# bidirectional_audio_v4_0_AFE.net
KiCad netlist of a schematic drawn in Altium Designer
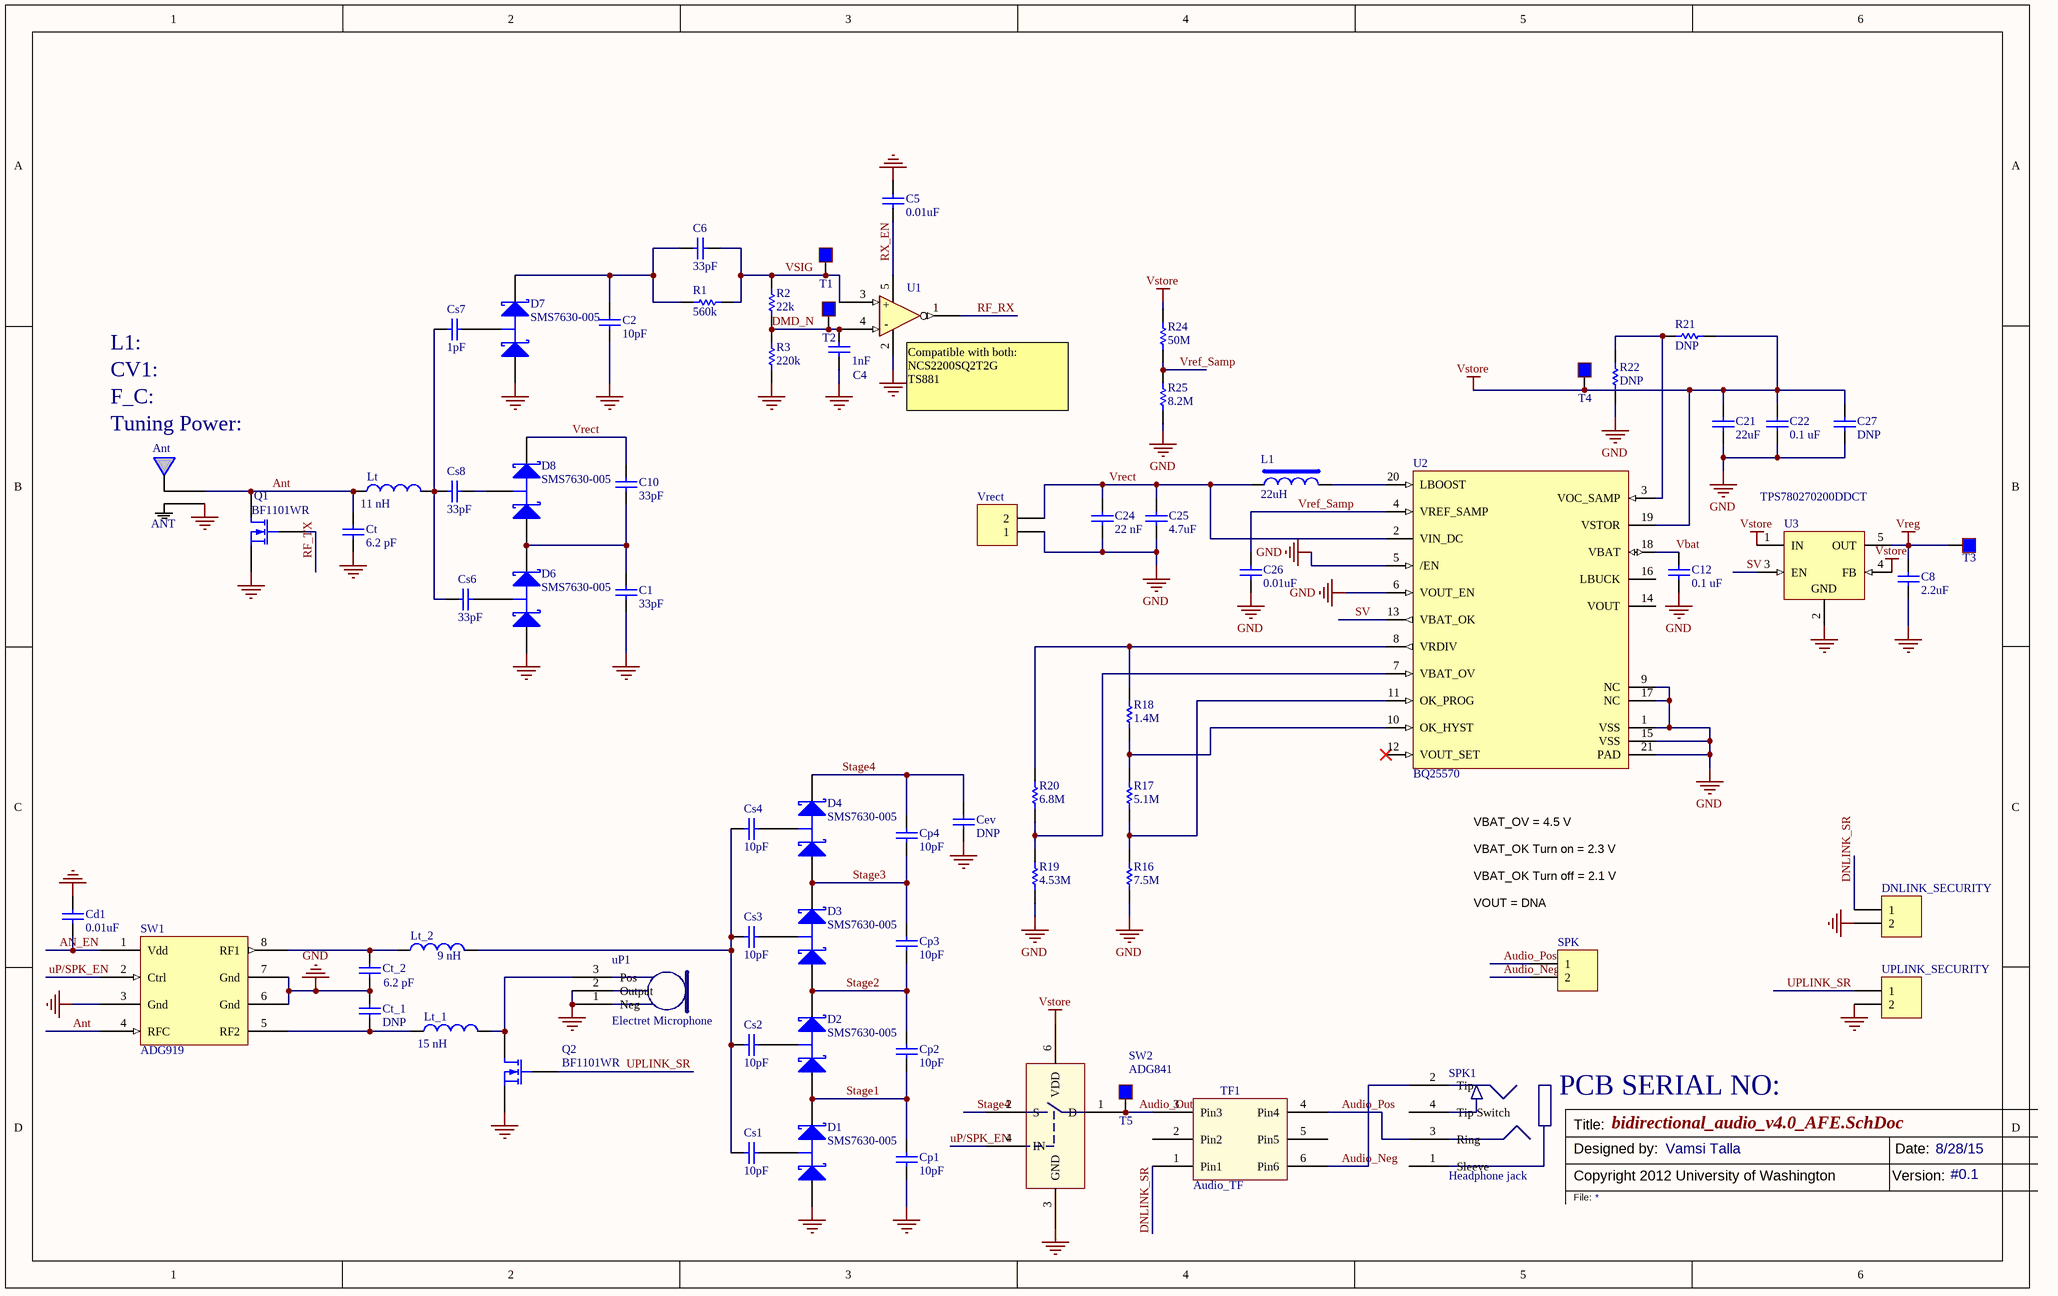
[diagram p0: bidirectional_audio_v4.0_AFE.SchDoc]

(export (version "E")
  (design (tool "Eeschema 10.0.6"))
  (components
    (comp (ref "Ant")
      (value "ANT")
      (footprint "PIFA_915MHz")
      (libsource (lib "bidirectional_audio") (part "ANT"))
    )
    (comp (ref "C1")
      (value "33pF")
      (footprint "0402")
      (description "Ceramic Capacitor (Surface Mount)")
      (fields
        (field (name "DIGI-KEY PART NUMBER") "712-1297-1-ND")
        (field (name "MANUFACTURER") "Johanson Technology Inc.")
      )
      (libsource (lib "WISP_AD10") (part "Cap"))
    )
    (comp (ref "C2")
      (value "10pF")
      (footprint "0402")
      (description "Ceramic Capacitor (Surface Mount)")
      (fields
        (field (name "DIGI-KEY PART NUMBER") "712-1252-1-ND")
        (field (name "MANUFACTURER") "Johanson Technology Inc.")
      )
      (libsource (lib "WISP_AD10") (part "Cap"))
    )
    (comp (ref "C4")
      (value "1nF")
      (footprint "0402")
      (description "Ceramic Capacitor (Surface Mount)")
      (fields
        (field (name "DIGI-KEY PART NUMBER") "490-6189-1-ND")
        (field (name "MANUFACTURER") "Murata Electronics North America")
      )
      (libsource (lib "WISP_AD10") (part "Cap"))
    )
    (comp (ref "C5")
      (value "0.01uF")
      (footprint "0402")
      (description "Ceramic Capacitor (Surface Mount)")
      (fields
        (field (name "DIGI-KEY PART NUMBER") "1276-1495-1-ND")
        (field (name "MANUFACTURER") "Samsung Electro-Mechanics America, Inc.")
      )
      (libsource (lib "WISP_AD10") (part "Cap"))
    )
    (comp (ref "C6")
      (value "33pF")
      (footprint "0402")
      (description "Ceramic Capacitor (Surface Mount)")
      (fields
        (field (name "DIGI-KEY PART NUMBER") "712-1297-1-ND")
        (field (name "MANUFACTURER") "Johanson Technology Inc.")
      )
      (libsource (lib "WISP_AD10") (part "Cap"))
    )
    (comp (ref "C8")
      (value "2.2uF")
      (footprint "0402")
      (description "Ceramic Capacitor (Surface Mount)")
      (fields
        (field (name "DIGI-KEY PART NUMBER") "478-7885-1-ND")
        (field (name "MANUFACTURER") "AVX Corporation")
      )
      (libsource (lib "WISP_AD10") (part "Cap"))
    )
    (comp (ref "C10")
      (value "33pF")
      (footprint "0402")
      (description "Ceramic Capacitor (Surface Mount)")
      (fields
        (field (name "DIGI-KEY PART NUMBER") "712-1297-1-ND")
        (field (name "MANUFACTURER") "Johanson Technology Inc.")
      )
      (libsource (lib "WISP_AD10") (part "Cap"))
    )
    (comp (ref "C12")
      (value "0.1 uF")
      (footprint "0402")
      (description "Ceramic Capacitor (Surface Mount)")
      (fields
        (field (name "DIGI-KEY PART NUMBER") "490-6327-1-ND")
        (field (name "MANUFACTURER") "Murata Electronics North America")
      )
      (libsource (lib "WISP_AD10") (part "Cap"))
    )
    (comp (ref "C21")
      (value "22uF")
      (footprint "0805-W")
      (description "Ceramic Capacitor (Surface Mount)")
      (fields
        (field (name "DIGI-KEY PART NUMBER") "1276-2867-1-ND")
        (field (name "MANUFACTURER") "Samsung Electro-Mechanics America, Inc.")
      )
      (libsource (lib "WISP_AD10") (part "Cap"))
    )
    (comp (ref "C22")
      (value "0.1 uF")
      (footprint "0402")
      (description "Ceramic Capacitor (Surface Mount)")
      (fields
        (field (name "DIGI-KEY PART NUMBER") "490-6327-1-ND")
        (field (name "MANUFACTURER") "Murata Electronics North America")
      )
      (libsource (lib "WISP_AD10") (part "Cap"))
    )
    (comp (ref "C24")
      (value "22 nF")
      (footprint "0402")
      (description "Ceramic Capacitor (Surface Mount)")
      (fields
        (field (name "DIGI-KEY PART NUMBER") "478-3666-1-ND")
        (field (name "MANUFACTURER") "AVX Corporation")
      )
      (libsource (lib "WISP_AD10") (part "Cap"))
    )
    (comp (ref "C25")
      (value "4.7uF")
      (footprint "0402")
      (description "Ceramic Capacitor (Surface Mount)")
      (fields
        (field (name "DIGI-KEY PART NUMBER") "445-5947-1-ND")
        (field (name "MANUFACTURER") "TDK Corporation")
      )
      (libsource (lib "WISP_AD10") (part "Cap"))
    )
    (comp (ref "C26")
      (value "0.01uF")
      (footprint "0402")
      (description "Ceramic Capacitor (Surface Mount)")
      (fields
        (field (name "DIGI-KEY PART NUMBER") "1276-1495-1-ND")
        (field (name "MANUFACTURER") "Samsung Electro-Mechanics America, Inc.")
      )
      (libsource (lib "WISP_AD10") (part "Cap"))
    )
    (comp (ref "C27")
      (value "DNP")
      (footprint "0805-W")
      (description "Ceramic Capacitor (Surface Mount)")
      (fields
        (field (name "MANUFACTURER") "Generic Ceramic Chip Cap (TBD)")
        (field (name "Comment") "Cstore2")
      )
      (libsource (lib "WISP_AD10") (part "Cap"))
    )
    (comp (ref "Cd1")
      (value "0.01uF")
      (footprint "0402")
      (description "Ceramic Capacitor (Surface Mount)")
      (fields
        (field (name "DIGI-KEY PART NUMBER") "1276-1495-1-ND")
        (field (name "MANUFACTURER") "Samsung Electro-Mechanics America, Inc.")
      )
      (libsource (lib "WISP_AD10") (part "Cap"))
    )
    (comp (ref "Cev")
      (value "DNP")
      (footprint "0402")
      (description "Ceramic Capacitor (Surface Mount)")
      (fields
        (field (name "MANUFACTURER") "Generic Ceramic Chip Cap (TBD)")
        (field (name "Comment") "Cout_env")
      )
      (libsource (lib "WISP_AD10") (part "Cap"))
    )
    (comp (ref "Cp1")
      (value "10pF")
      (footprint "0402")
      (description "Ceramic Capacitor (Surface Mount)")
      (fields
        (field (name "DIGI-KEY PART NUMBER") "712-1252-1-ND")
        (field (name "MANUFACTURER") "Johanson Technology Inc.")
      )
      (libsource (lib "WISP_AD10") (part "Cap"))
    )
    (comp (ref "Cp2")
      (value "10pF")
      (footprint "0402")
      (description "Ceramic Capacitor (Surface Mount)")
      (fields
        (field (name "DIGI-KEY PART NUMBER") "712-1252-1-ND")
        (field (name "MANUFACTURER") "Johanson Technology Inc.")
      )
      (libsource (lib "WISP_AD10") (part "Cap"))
    )
    (comp (ref "Cp3")
      (value "10pF")
      (footprint "0402")
      (description "Ceramic Capacitor (Surface Mount)")
      (fields
        (field (name "DIGI-KEY PART NUMBER") "712-1252-1-ND")
        (field (name "MANUFACTURER") "Johanson Technology Inc.")
      )
      (libsource (lib "WISP_AD10") (part "Cap"))
    )
    (comp (ref "Cp4")
      (value "10pF")
      (footprint "0402")
      (description "Ceramic Capacitor (Surface Mount)")
      (fields
        (field (name "DIGI-KEY PART NUMBER") "712-1252-1-ND")
        (field (name "MANUFACTURER") "Johanson Technology Inc.")
      )
      (libsource (lib "WISP_AD10") (part "Cap"))
    )
    (comp (ref "Cs1")
      (value "10pF")
      (footprint "0402")
      (description "Ceramic Capacitor (Surface Mount)")
      (fields
        (field (name "DIGI-KEY PART NUMBER") "712-1252-1-ND")
        (field (name "MANUFACTURER") "Johanson Technology Inc.")
      )
      (libsource (lib "WISP_AD10") (part "Cap"))
    )
    (comp (ref "Cs2")
      (value "10pF")
      (footprint "0402")
      (description "Ceramic Capacitor (Surface Mount)")
      (fields
        (field (name "DIGI-KEY PART NUMBER") "712-1252-1-ND")
        (field (name "MANUFACTURER") "Johanson Technology Inc.")
      )
      (libsource (lib "WISP_AD10") (part "Cap"))
    )
    (comp (ref "Cs3")
      (value "10pF")
      (footprint "0402")
      (description "Ceramic Capacitor (Surface Mount)")
      (fields
        (field (name "DIGI-KEY PART NUMBER") "712-1252-1-ND")
        (field (name "MANUFACTURER") "Johanson Technology Inc.")
      )
      (libsource (lib "WISP_AD10") (part "Cap"))
    )
    (comp (ref "Cs4")
      (value "10pF")
      (footprint "0402")
      (description "Ceramic Capacitor (Surface Mount)")
      (fields
        (field (name "DIGI-KEY PART NUMBER") "712-1252-1-ND")
        (field (name "MANUFACTURER") "Johanson Technology Inc.")
      )
      (libsource (lib "WISP_AD10") (part "Cap"))
    )
    (comp (ref "Cs6")
      (value "33pF")
      (footprint "0402")
      (description "Ceramic Capacitor (Surface Mount)")
      (fields
        (field (name "DIGI-KEY PART NUMBER") "712-1297-1-ND")
        (field (name "MANUFACTURER") "Johanson Technology Inc.")
      )
      (libsource (lib "WISP_AD10") (part "Cap"))
    )
    (comp (ref "Cs7")
      (value "1pF")
      (footprint "0402")
      (description "Ceramic Capacitor (Surface Mount)")
      (fields
        (field (name "DIGI-KEY PART NUMBER") "712-1266-1-ND")
        (field (name "MANUFACTURER") "Johanson Technology Inc.")
      )
      (libsource (lib "WISP_AD10") (part "Cap"))
    )
    (comp (ref "Cs8")
      (value "33pF")
      (footprint "0402")
      (description "Ceramic Capacitor (Surface Mount)")
      (fields
        (field (name "DIGI-KEY PART NUMBER") "712-1297-1-ND")
        (field (name "MANUFACTURER") "Johanson Technology Inc.")
      )
      (libsource (lib "WISP_AD10") (part "Cap"))
    )
    (comp (ref "Ct")
      (value "6.2 pF")
      (footprint "0402")
      (description "Ceramic Capacitor (Surface Mount)")
      (fields
        (field (name "DIGI-KEY PART NUMBER") "712-1290-1-ND")
        (field (name "MANUFACTURER") "Johanson Technology Inc.")
      )
      (libsource (lib "WISP_AD10") (part "Cap"))
    )
    (comp (ref "Ct_1")
      (value "DNP")
      (footprint "0402")
      (description "Ceramic Capacitor (Surface Mount)")
      (fields (field (name "MANUFACTURER") "Generic Ceramic Chip Cap (TBD)") (field (name "Comment") "Cap"))
      (libsource (lib "WISP_AD10") (part "Cap"))
    )
    (comp (ref "Ct_2")
      (value "6.2 pF")
      (footprint "0402")
      (description "Ceramic Capacitor (Surface Mount)")
      (fields
        (field (name "DIGI-KEY PART NUMBER") "712-1290-1-ND")
        (field (name "MANUFACTURER") "Johanson Technology Inc.")
      )
      (libsource (lib "WISP_AD10") (part "Cap"))
    )
    (comp (ref "D1")
      (value "SMS7630-005")
      (footprint "SOT23 - N")
      (description "Agilent Schottky Diode, Two in Series, Small Package SOT-323")
      (fields
        (field (name "DIGI-KEY PART NUMBER") "863-1699-1-ND")
        (field (name "MANUFACTURER") "Skyworks Solutions Inc.")
      )
      (libsource (lib "WISP_AD10") (part "SMS7630-005"))
    )
    (comp (ref "D2")
      (value "SMS7630-005")
      (footprint "SOT23 - N")
      (description "Agilent Schottky Diode, Two in Series, Small Package SOT-323")
      (fields
        (field (name "DIGI-KEY PART NUMBER") "863-1699-1-ND")
        (field (name "MANUFACTURER") "Skyworks Solutions Inc.")
      )
      (libsource (lib "WISP_AD10") (part "SMS7630-005"))
    )
    (comp (ref "D3")
      (value "SMS7630-005")
      (footprint "SOT23 - N")
      (description "Agilent Schottky Diode, Two in Series, Small Package SOT-323")
      (fields
        (field (name "DIGI-KEY PART NUMBER") "863-1699-1-ND")
        (field (name "MANUFACTURER") "Skyworks Solutions Inc.")
      )
      (libsource (lib "WISP_AD10") (part "SMS7630-005"))
    )
    (comp (ref "D4")
      (value "SMS7630-005")
      (footprint "SOT23 - N")
      (description "Agilent Schottky Diode, Two in Series, Small Package SOT-323")
      (fields
        (field (name "DIGI-KEY PART NUMBER") "863-1699-1-ND")
        (field (name "MANUFACTURER") "Skyworks Solutions Inc.")
      )
      (libsource (lib "WISP_AD10") (part "SMS7630-005"))
    )
    (comp (ref "D6")
      (value "SMS7630-005")
      (footprint "SOT23 - N")
      (description "Agilent Schottky Diode, Two in Series, Small Package SOT-323")
      (fields
        (field (name "DIGI-KEY PART NUMBER") "863-1699-1-ND")
        (field (name "MANUFACTURER") "Skyworks Solutions Inc.")
      )
      (libsource (lib "WISP_AD10") (part "SMS7630-005"))
    )
    (comp (ref "D7")
      (value "SMS7630-005")
      (footprint "SOT23 - N")
      (description "Agilent Schottky Diode, Two in Series, Small Package SOT-323")
      (fields
        (field (name "DIGI-KEY PART NUMBER") "863-1699-1-ND")
        (field (name "MANUFACTURER") "Skyworks Solutions Inc.")
      )
      (libsource (lib "WISP_AD10") (part "SMS7630-005"))
    )
    (comp (ref "D8")
      (value "SMS7630-005")
      (footprint "SOT23 - N")
      (description "Agilent Schottky Diode, Two in Series, Small Package SOT-323")
      (fields
        (field (name "DIGI-KEY PART NUMBER") "863-1699-1-ND")
        (field (name "MANUFACTURER") "Skyworks Solutions Inc.")
      )
      (libsource (lib "WISP_AD10") (part "SMS7630-005"))
    )
    (comp (ref "DNLINK_SECURITY")
      (value "MHDR1X2")
      (footprint "MHDR1X2")
      (description "Header, 2-Pin")
      (fields
        (field (name "DIGI-KEY PART NUMBER") "609-4434-ND")
        (field (name "MANUFACTURER") "FCI")
        (field (name "PUBLISHER") "Altium Limited")
      )
      (libsource (lib "Miscellaneous Connectors") (part "MHDR1X2"))
    )
    (comp (ref "L1")
      (value "22uH")
      (footprint "LPS4018")
      (description "Inductor (Surface Mount)")
      (fields (field (name "DIGI-KEY PART NUMBER") "NA") (field (name "MANUFACTURER") "Coil Craft"))
      (libsource (lib "WISP_AD10") (part "Ind_LPS4018"))
    )
    (comp (ref "Lt")
      (value "11 nH")
      (footprint "0402")
      (description "Inductor (Surface Mount)")
      (fields (field (name "MANUFACTURER PART NUMBER") "0402HP-11NXGE") (field (name "Comment") "L_Ant_tune"))
      (libsource (lib "WISP_AD10") (part "Ind"))
    )
    (comp (ref "Lt_1")
      (value "15 nH")
      (footprint "0402")
      (description "Inductor (Surface Mount)")
      (fields (field (name "MANUFACTURER PART NUMBER") "0402HP-15NXGE") (field (name "Comment") "Ind"))
      (libsource (lib "WISP_AD10") (part "Ind"))
    )
    (comp (ref "Lt_2")
      (value "9 nH")
      (footprint "0402")
      (description "Inductor (Surface Mount)")
      (fields (field (name "MANUFACTURER PART NUMBER") "0402HP-9N0XGE") (field (name "Comment") "Ind"))
      (libsource (lib "WISP_AD10") (part "Ind"))
    )
    (comp (ref "Q1")
      (value "BF1101WR")
      (footprint "SOT343R")
      (description "N-Channel Dual-Gate Mos-Fets MOSFET, SOT343R")
      (fields
        (field (name "DIGI-KEY PART NUMBER") "568-6140-1-ND")
        (field (name "MANUFACTURER PART NUMBER") "BF1101WR,115")
      )
      (libsource (lib "WISP_AD10") (part "BF1101WR"))
    )
    (comp (ref "Q2")
      (value "BF1101WR")
      (footprint "SOT343R")
      (description "N-Channel Dual-Gate Mos-Fets MOSFET, SOT343R")
      (fields
        (field (name "DIGI-KEY PART NUMBER") "568-6140-1-ND")
        (field (name "MANUFACTURER PART NUMBER") "BF1101WR,115")
      )
      (libsource (lib "WISP_AD10") (part "BF1101WR"))
    )
    (comp (ref "R1")
      (value "560k")
      (footprint "0402")
      (description "Chip Resistor (Surface Mount)")
      (fields
        (field (name "MANUFACTURER") "Yageo")
        (field (name "MANUFACTURER PART NUMBER") "RC0402FR-07560KL")
      )
      (libsource (lib "WISP_AD10") (part "Res"))
    )
    (comp (ref "R2")
      (value "22k")
      (footprint "0402")
      (description "Chip Resistor (Surface Mount)")
      (fields
        (field (name "MANUFACTURER") "Yageo")
        (field (name "MANUFACTURER PART NUMBER") "RC0402FR-0722KL")
      )
      (libsource (lib "WISP_AD10") (part "Res"))
    )
    (comp (ref "R3")
      (value "220k")
      (footprint "0402")
      (description "Chip Resistor (Surface Mount)")
      (fields
        (field (name "MANUFACTURER") "Yageo")
        (field (name "MANUFACTURER PART NUMBER") "RC0402FR-07220KL")
      )
      (libsource (lib "WISP_AD10") (part "Res"))
    )
    (comp (ref "R16")
      (value "7.5M")
      (footprint "0402")
      (description "Chip Resistor (Surface Mount)")
      (fields
        (field (name "MANUFACTURER") "Vishay Dale")
        (field (name "MANUFACTURER PART NUMBER") "CRCW04027M50JNED")
      )
      (libsource (lib "WISP_AD10") (part "Res"))
    )
    (comp (ref "R17")
      (value "5.1M")
      (footprint "0402")
      (description "Chip Resistor (Surface Mount)")
      (fields
        (field (name "MANUFACTURER") "Vishay Dale")
        (field (name "MANUFACTURER PART NUMBER") "CRCW04025M10JNED")
      )
      (libsource (lib "WISP_AD10") (part "Res"))
    )
    (comp (ref "R18")
      (value "1.4M")
      (footprint "0402")
      (description "Chip Resistor (Surface Mount)")
      (fields
        (field (name "MANUFACTURER") "Vishay Dale")
        (field (name "MANUFACTURER PART NUMBER") "CRCW04021M40FKED")
      )
      (libsource (lib "WISP_AD10") (part "Res"))
    )
    (comp (ref "R19")
      (value "4.53M")
      (footprint "0402")
      (description "Chip Resistor (Surface Mount)")
      (fields
        (field (name "MANUFACTURER") "Vishay Dale")
        (field (name "MANUFACTURER PART NUMBER") "CRCW04024M53FKED")
      )
      (libsource (lib "WISP_AD10") (part "Res"))
    )
    (comp (ref "R20")
      (value "6.8M")
      (footprint "0402")
      (description "Chip Resistor (Surface Mount)")
      (fields
        (field (name "MANUFACTURER") "Samsung Electro-Mechanics America, Inc.")
        (field (name "MANUFACTURER PART NUMBER") "RC1005J685CS")
      )
      (libsource (lib "WISP_AD10") (part "Res"))
    )
    (comp (ref "R21")
      (value "DNP")
      (footprint "0402")
      (description "Chip Resistor (Surface Mount)")
      (fields (field (name "MANUFACTURER") "Generic Chip Res (TBD)") (field (name "Comment") "R_80%"))
      (libsource (lib "WISP_AD10") (part "Res"))
    )
    (comp (ref "R22")
      (value "DNP")
      (footprint "0402")
      (description "Chip Resistor (Surface Mount)")
      (fields (field (name "MANUFACTURER") "Generic Chip Res (TBD)") (field (name "Comment") "R_50%"))
      (libsource (lib "WISP_AD10") (part "Res"))
    )
    (comp (ref "R24")
      (value "50M")
      (footprint "0402")
      (description "Chip Resistor (Surface Mount)")
      (fields
        (field (name "MANUFACTURER") "Stackpole Electronics Inc.")
        (field (name "MANUFACTURER PART NUMBER") "HMC0402JT50M0")
      )
      (libsource (lib "WISP_AD10") (part "Res"))
    )
    (comp (ref "R25")
      (value "8.2M")
      (footprint "0402")
      (description "Chip Resistor (Surface Mount)")
      (fields
        (field (name "MANUFACTURER") "Vishay Dale")
        (field (name "MANUFACTURER PART NUMBER") "CRCW04028M20JNED")
      )
      (libsource (lib "WISP_AD10") (part "Res"))
    )
    (comp (ref "SPK")
      (value "MHDR1X2")
      (footprint "MHDR1X2")
      (description "Header, 2-Pin")
      (fields
        (field (name "DIGI-KEY PART NUMBER") "609-4434-ND")
        (field (name "MANUFACTURER") "FCI")
        (field (name "PUBLISHER") "Altium Limited")
      )
      (libsource (lib "Miscellaneous Connectors") (part "MHDR1X2"))
    )
    (comp (ref "SPK1")
      (value "Headphone jack")
      (footprint "CONN_JACK")
      (fields
        (field (name "DIGI-KEY PART NUMBER") "CP-3524SJGRCT-ND")
        (field (name "MANUFACTURER") "CUI Inc.")
        (field (name "MANUFACTURER PART NUMBER") "SJ-3524-SMT-TR-GR")
      )
      (libsource (lib "bidirectional_audio") (part "CONN_JACK"))
    )
    (comp (ref "SW1")
      (value "ADG919")
      (footprint "MSOP_8pin")
      (description "RF 2:1 MUX/SPDT Reflective")
      (fields
        (field (name "DIGI-KEY PART NUMBER") "ADG919BRMZ-ND")
        (field (name "MANUFACTURER PART NUMBER") "ADG919BRMZ")
      )
      (libsource (lib "WispLib") (part "ADG919"))
    )
    (comp (ref "SW2")
      (value "ADG841")
      (footprint "SC70-6")
      (description "Audio Switch")
      (fields
        (field (name "MANUFACTURER PART NUMBER") "ADG841YKSZ-500RL7")
        (field (name "MANUFACTURER") "Analog Devices Inc.")
      )
      (libsource (lib "bidirectional_audio") (part "ADG841"))
    )
    (comp (ref "T1")
      (value "Test Point SMT")
      (footprint "SMT_TESTPOINT_2MM")
      (description "Test Point, Flat Pad")
      (fields
        (field (name "DIGI-KEY PART NUMBER") "A106145CT-ND")
        (field (name "MANUFACTURER PART NUMBER") "1625854-3")
      )
      (libsource (lib "WISP_AD10") (part "Test Point SMT"))
    )
    (comp (ref "T2")
      (value "Test Point SMT")
      (footprint "SMT_TESTPOINT_2MM")
      (description "Test Point, Flat Pad")
      (fields
        (field (name "DIGI-KEY PART NUMBER") "A106145CT-ND")
        (field (name "MANUFACTURER PART NUMBER") "1625854-3")
      )
      (libsource (lib "WISP_AD10") (part "Test Point SMT"))
    )
    (comp (ref "T3")
      (value "Test Point SMT")
      (footprint "SMT_TESTPOINT_2MM")
      (description "Test Point, Flat Pad")
      (fields
        (field (name "DIGI-KEY PART NUMBER") "A106145CT-ND")
        (field (name "MANUFACTURER PART NUMBER") "1625854-3")
      )
      (libsource (lib "") (part "Test Point SMT_1"))
    )
    (comp (ref "T4")
      (value "Test Point SMT")
      (footprint "SMT_TESTPOINT_2MM")
      (description "Test Point, Flat Pad")
      (fields
        (field (name "DIGI-KEY PART NUMBER") "A106145CT-ND")
        (field (name "MANUFACTURER PART NUMBER") "1625854-3")
      )
      (libsource (lib "WISP_AD10") (part "Test Point SMT"))
    )
    (comp (ref "T5")
      (value "Test Point SMT")
      (footprint "SMT_TESTPOINT_2MM")
      (description "Test Point, Flat Pad")
      (fields
        (field (name "DIGI-KEY PART NUMBER") "A106145CT-ND")
        (field (name "MANUFACTURER PART NUMBER") "1625854-3")
      )
      (libsource (lib "WISP_AD10") (part "Test Point SMT"))
    )
    (comp (ref "TF1")
      (value "Audio_TF")
      (footprint "Audio_TF")
      (description "Audio Transformer by Triad")
      (fields
        (field (name "DIGI-KEY PART NUMBER") "237-1146-ND")
        (field (name "MANUFACTURER") "Triad Magnetics")
      )
      (libsource (lib "bidirectional_audio") (part "Audio_TF"))
    )
    (comp (ref "U1")
      (value "Comparator")
      (footprint "SC70-5")
      (description "6uA Comparator")
      (fields
        (field (name "DIGI-KEY PART NUMBER") "568-7526-1-ND")
        (field (name "MANUFACTURER") "NXP Semiconductors")
      )
      (libsource (lib "WISP_AD10") (part "NCS2200"))
    )
    (comp (ref "U2")
      (value "BQ25570")
      (footprint "BQ25570")
      (description "Boost Charger")
      (fields
        (field (name "DIGI-KEY PART NUMBER") "296-37014-1-ND")
        (field (name "MANUFACTURER") "Texas Instruments")
      )
      (libsource (lib "WISP_AD10") (part "BQ25570"))
    )
    (comp (ref "U3")
      (value "TPS780270200DDCT")
      (footprint "TI-DDC5_L")
      (fields
        (field (name "MANUFACTURER") "Texas Instruments")
        (field (name "DIGI-KEY PART NUMBER") "296-32564-1-ND")
      )
      (libsource (lib "Altium Content Vault") (part "CMP-0394-01119-1"))
    )
    (comp (ref "uP1")
      (value "Electret Microphone")
      (footprint "uP_23024")
      (fields
        (field (name "DIGI-KEY PART NUMBER") "423-1160-ND")
        (field (name "MANUFACTURER") "Knowles")
        (field (name "MANUFACTURER PART NUMBER") "EK-23024-000")
      )
      (libsource (lib "bidirectional_audio") (part "UP_Knowles_23024"))
    )
    (comp (ref "UPLINK_SECURITY")
      (value "MHDR1X2")
      (footprint "MHDR1X2")
      (description "Header, 2-Pin")
      (fields
        (field (name "DIGI-KEY PART NUMBER") "609-4434-ND")
        (field (name "MANUFACTURER") "FCI")
        (field (name "PUBLISHER") "Altium Limited")
      )
      (libsource (lib "Miscellaneous Connectors") (part "MHDR1X2"))
    )
    (comp (ref "Vrect")
      (value "MHDR1X2")
      (footprint "MHDR1X2")
      (description "Header, 2-Pin")
      (fields
        (field (name "DIGI-KEY PART NUMBER") "609-4434-ND")
        (field (name "MANUFACTURER") "FCI")
        (field (name "PUBLISHER") "Altium Limited")
      )
      (libsource (lib "") (part "MHDR1X2_1"))
    )
  )
  (nets
    (net (code "1") (name "/AN_EN") (class "Default")
      (node (ref "Cd1") (pin "1") (pinfunction "1_1") (pintype "passive"))
      (node (ref "SW1") (pin "1") (pinfunction "Vdd_1") (pintype "power_in"))
    )
    (net (code "2") (name "/Ant") (class "Default")
      (node (ref "Ant") (pin "1") (pinfunction "Feed_1") (pintype "passive"))
      (node (ref "Ct") (pin "1") (pinfunction "1_1") (pintype "passive"))
      (node (ref "Lt") (pin "1") (pinfunction "1_1") (pintype "passive"))
      (node (ref "Q1") (pin "2") (pinfunction "D_2") (pintype "passive"))
      (node (ref "SW1") (pin "4") (pinfunction "RFC_4") (pintype "input"))
    )
    (net (code "3") (name "/Audio_Neg") (class "Default")
      (node (ref "SPK") (pin "2") (pinfunction "2_2") (pintype "passive"))
      (node (ref "SPK1") (pin "2") (pinfunction "Tip_2") (pintype "passive"))
      (node (ref "TF1") (pin "6") (pinfunction "Pin6_6") (pintype "passive"))
    )
    (net (code "4") (name "/Audio_Out") (class "Default")
      (node (ref "SW2") (pin "1") (pinfunction "D_1") (pintype "passive"))
      (node (ref "T5") (pin "1") (pintype "passive"))
      (node (ref "TF1") (pin "3") (pinfunction "Pin3_3") (pintype "passive"))
    )
    (net (code "5") (name "/Audio_Pos") (class "Default")
      (node (ref "SPK") (pin "1") (pinfunction "1_1") (pintype "passive"))
      (node (ref "SPK1") (pin "3") (pinfunction "Ring_3") (pintype "passive"))
      (node (ref "TF1") (pin "4") (pinfunction "Pin4_4") (pintype "passive"))
    )
    (net (code "6") (name "/DMD_N") (class "Default")
      (node (ref "C4") (pin "1") (pinfunction "1_1") (pintype "passive"))
      (node (ref "R2") (pin "1") (pinfunction "1_1") (pintype "passive"))
      (node (ref "R3") (pin "2") (pinfunction "2_2") (pintype "passive"))
      (node (ref "T2") (pin "1") (pintype "passive"))
      (node (ref "U1") (pin "4") (pinfunction "In-_4") (pintype "input"))
    )
    (net (code "7") (name "/DNLINK_SR") (class "Default")
      (node (ref "DNLINK_SECURITY") (pin "1") (pinfunction "1_1") (pintype "passive"))
      (node (ref "TF1") (pin "1") (pinfunction "Pin1_1") (pintype "passive"))
    )
    (net (code "8") (name "/RF_RX") (class "Default")
      (node (ref "U1") (pin "1") (pinfunction "OUT_1") (pintype "output"))
    )
    (net (code "9") (name "/RF_TX") (class "Default")
      (node (ref "Q1") (pin "3") (pinfunction "G_3") (pintype "passive"))
    )
    (net (code "10") (name "/RX_EN") (class "Default")
      (node (ref "C5") (pin "1") (pinfunction "1_1") (pintype "passive"))
      (node (ref "U1") (pin "5") (pinfunction "VDD_5") (pintype "power_in"))
    )
    (net (code "11") (name "/SV") (class "Default")
      (node (ref "U2") (pin "13") (pinfunction "VBAT_OK_13") (pintype "output"))
      (node (ref "U3") (pin "3") (pinfunction "EN_3") (pintype "input"))
    )
    (net (code "12") (name "/Stage1") (class "Default")
      (node (ref "Cp1") (pin "2") (pinfunction "2_2") (pintype "passive"))
      (node (ref "Cp2") (pin "1") (pinfunction "1_1") (pintype "passive"))
      (node (ref "D1") (pin "2") (pinfunction "K_2") (pintype "passive"))
      (node (ref "D2") (pin "1") (pinfunction "A_1") (pintype "passive"))
    )
    (net (code "13") (name "/Stage2") (class "Default")
      (node (ref "Cp2") (pin "2") (pinfunction "2_2") (pintype "passive"))
      (node (ref "Cp3") (pin "1") (pinfunction "1_1") (pintype "passive"))
      (node (ref "D2") (pin "2") (pinfunction "K_2") (pintype "passive"))
      (node (ref "D3") (pin "1") (pinfunction "A_1") (pintype "passive"))
    )
    (net (code "14") (name "/Stage3") (class "Default")
      (node (ref "Cp3") (pin "2") (pinfunction "2_2") (pintype "passive"))
      (node (ref "Cp4") (pin "1") (pinfunction "1_1") (pintype "passive"))
      (node (ref "D3") (pin "2") (pinfunction "K_2") (pintype "passive"))
      (node (ref "D4") (pin "1") (pinfunction "A_1") (pintype "passive"))
    )
    (net (code "15") (name "/Stage4") (class "Default")
      (node (ref "Cev") (pin "1") (pinfunction "1_1") (pintype "passive"))
      (node (ref "Cp4") (pin "2") (pinfunction "2_2") (pintype "passive"))
      (node (ref "D4") (pin "2") (pinfunction "K_2") (pintype "passive"))
      (node (ref "SW2") (pin "2") (pinfunction "S_2") (pintype "passive"))
    )
    (net (code "16") (name "/UPLINK_SR") (class "Default")
      (node (ref "Q2") (pin "3") (pinfunction "G_3") (pintype "passive"))
      (node (ref "UPLINK_SECURITY") (pin "1") (pinfunction "1_1") (pintype "passive"))
    )
    (net (code "17") (name "/VSIG") (class "Default")
      (node (ref "C6") (pin "2") (pinfunction "2_2") (pintype "passive"))
      (node (ref "R1") (pin "1") (pinfunction "1_1") (pintype "passive"))
      (node (ref "R2") (pin "2") (pinfunction "2_2") (pintype "passive"))
      (node (ref "T1") (pin "1") (pintype "passive"))
      (node (ref "U1") (pin "3") (pinfunction "IN+_3") (pintype "input"))
    )
    (net (code "18") (name "/Vbat") (class "Default")
      (node (ref "C12") (pin "2") (pinfunction "2_2") (pintype "passive"))
      (node (ref "U2") (pin "18") (pinfunction "VBAT_18") (pintype "bidirectional"))
    )
    (net (code "19") (name "/Vrect") (class "Default")
      (node (ref "C10") (pin "2") (pinfunction "2_2") (pintype "passive"))
      (node (ref "C24") (pin "2") (pinfunction "2_2") (pintype "passive"))
      (node (ref "C25") (pin "2") (pinfunction "2_2") (pintype "passive"))
      (node (ref "D8") (pin "2") (pinfunction "K_2") (pintype "passive"))
      (node (ref "L1") (pin "1") (pinfunction "1_1") (pintype "passive"))
      (node (ref "U2") (pin "2") (pinfunction "VIN_DC_2") (pintype "passive"))
      (node (ref "Vrect") (pin "2") (pinfunction "2_2") (pintype "passive"))
    )
    (net (code "20") (name "/Vref_Samp") (class "Default")
      (node (ref "C26") (pin "2") (pinfunction "2_2") (pintype "passive"))
      (node (ref "R24") (pin "1") (pinfunction "1_1") (pintype "passive"))
      (node (ref "R25") (pin "2") (pinfunction "2_2") (pintype "passive"))
      (node (ref "U2") (pin "4") (pinfunction "VREF_SAMP_4") (pintype "input"))
    )
    (net (code "21") (name "/uP{slash}SPK_EN") (class "Default")
      (node (ref "SW1") (pin "2") (pinfunction "Ctrl_2") (pintype "input"))
      (node (ref "SW2") (pin "4") (pinfunction "IN_4") (pintype "passive"))
    )
    (net (code "22") (name "GND") (class "Default")
      (node (ref "Ant") (pin "2") (pinfunction "Gnd_2") (pintype "passive"))
      (node (ref "C1") (pin "1") (pinfunction "1_1") (pintype "passive"))
      (node (ref "C12") (pin "1") (pinfunction "1_1") (pintype "passive"))
      (node (ref "C2") (pin "1") (pinfunction "1_1") (pintype "passive"))
      (node (ref "C21") (pin "1") (pinfunction "1_1") (pintype "passive"))
      (node (ref "C22") (pin "1") (pinfunction "1_1") (pintype "passive"))
      (node (ref "C24") (pin "1") (pinfunction "1_1") (pintype "passive"))
      (node (ref "C25") (pin "1") (pinfunction "1_1") (pintype "passive"))
      (node (ref "C26") (pin "1") (pinfunction "1_1") (pintype "passive"))
      (node (ref "C27") (pin "1") (pinfunction "1_1") (pintype "passive"))
      (node (ref "C4") (pin "2") (pinfunction "2_2") (pintype "passive"))
      (node (ref "C5") (pin "2") (pinfunction "2_2") (pintype "passive"))
      (node (ref "C8") (pin "1") (pinfunction "1_1") (pintype "passive"))
      (node (ref "Cd1") (pin "2") (pinfunction "2_2") (pintype "passive"))
      (node (ref "Cev") (pin "2") (pinfunction "2_2") (pintype "passive"))
      (node (ref "Cp1") (pin "1") (pinfunction "1_1") (pintype "passive"))
      (node (ref "Ct") (pin "2") (pinfunction "2_2") (pintype "passive"))
      (node (ref "Ct_1") (pin "1") (pinfunction "1_1") (pintype "passive"))
      (node (ref "Ct_2") (pin "2") (pinfunction "2_2") (pintype "passive"))
      (node (ref "D1") (pin "1") (pinfunction "A_1") (pintype "passive"))
      (node (ref "D6") (pin "1") (pinfunction "A_1") (pintype "passive"))
      (node (ref "D7") (pin "1") (pinfunction "A_1") (pintype "passive"))
      (node (ref "DNLINK_SECURITY") (pin "2") (pinfunction "2_2") (pintype "passive"))
      (node (ref "Q1") (pin "1") (pinfunction "S_1") (pintype "passive"))
      (node (ref "Q2") (pin "1") (pinfunction "S_1") (pintype "passive"))
      (node (ref "R16") (pin "2") (pinfunction "2_2") (pintype "passive"))
      (node (ref "R19") (pin "2") (pinfunction "2_2") (pintype "passive"))
      (node (ref "R22") (pin "1") (pinfunction "1_1") (pintype "passive"))
      (node (ref "R25") (pin "1") (pinfunction "1_1") (pintype "passive"))
      (node (ref "R3") (pin "1") (pinfunction "1_1") (pintype "passive"))
      (node (ref "SW1") (pin "3") (pinfunction "Gnd_3") (pintype "power_in"))
      (node (ref "SW1") (pin "6") (pinfunction "Gnd_6") (pintype "power_in"))
      (node (ref "SW1") (pin "7") (pinfunction "Gnd_7") (pintype "power_in"))
      (node (ref "SW2") (pin "3") (pinfunction "GND_3") (pintype "passive"))
      (node (ref "U1") (pin "2") (pinfunction "Gnd_2") (pintype "power_in"))
      (node (ref "U2") (pin "1") (pinfunction "VSS_1") (pintype "passive"))
      (node (ref "U2") (pin "15") (pinfunction "VSS_15") (pintype "passive"))
      (node (ref "U2") (pin "17") (pinfunction "NC_17") (pintype "passive"))
      (node (ref "U2") (pin "21") (pinfunction "PAD_21") (pintype "passive"))
      (node (ref "U2") (pin "5") (pinfunction "/EN_5") (pintype "input"))
      (node (ref "U2") (pin "6") (pinfunction "VOUT_EN_6") (pintype "input"))
      (node (ref "U2") (pin "9") (pinfunction "NC_9") (pintype "passive"))
      (node (ref "U3") (pin "2") (pinfunction "GND_2") (pintype "power_in"))
      (node (ref "UPLINK_SECURITY") (pin "2") (pinfunction "2_2") (pintype "passive"))
      (node (ref "Vrect") (pin "1") (pinfunction "1_1") (pintype "passive"))
      (node (ref "uP1") (pin "1") (pinfunction "Neg_1") (pintype "passive"))
      (node (ref "uP1") (pin "2") (pinfunction "Output_2") (pintype "passive"))
    )
    (net (code "23") (name "Net-(Cs1-Pad1)") (class "Default")
      (node (ref "Cs1") (pin "1") (pinfunction "1_1") (pintype "passive"))
      (node (ref "Cs2") (pin "1") (pinfunction "1_1") (pintype "passive"))
      (node (ref "Cs3") (pin "1") (pinfunction "1_1") (pintype "passive"))
      (node (ref "Cs4") (pin "1") (pinfunction "1_1") (pintype "passive"))
      (node (ref "Lt_2") (pin "2") (pinfunction "2_2") (pintype "passive"))
    )
    (net (code "24") (name "Net-(Cs6-Pad1)") (class "Default")
      (node (ref "Cs6") (pin "1") (pinfunction "1_1") (pintype "passive"))
      (node (ref "Cs7") (pin "1") (pinfunction "1_1") (pintype "passive"))
      (node (ref "Cs8") (pin "1") (pinfunction "1_1") (pintype "passive"))
      (node (ref "Lt") (pin "2") (pinfunction "2_2") (pintype "passive"))
    )
    (net (code "25") (name "Net-(D1-C)") (class "Default")
      (node (ref "Cs1") (pin "2") (pinfunction "2_2") (pintype "passive"))
      (node (ref "D1") (pin "3") (pinfunction "C_3") (pintype "passive"))
    )
    (net (code "26") (name "Net-(D2-C)") (class "Default")
      (node (ref "Cs2") (pin "2") (pinfunction "2_2") (pintype "passive"))
      (node (ref "D2") (pin "3") (pinfunction "C_3") (pintype "passive"))
    )
    (net (code "27") (name "Net-(D3-C)") (class "Default")
      (node (ref "Cs3") (pin "2") (pinfunction "2_2") (pintype "passive"))
      (node (ref "D3") (pin "3") (pinfunction "C_3") (pintype "passive"))
    )
    (net (code "28") (name "Net-(D4-C)") (class "Default")
      (node (ref "Cs4") (pin "2") (pinfunction "2_2") (pintype "passive"))
      (node (ref "D4") (pin "3") (pinfunction "C_3") (pintype "passive"))
    )
    (net (code "29") (name "Net-(D6-C)") (class "Default")
      (node (ref "Cs6") (pin "2") (pinfunction "2_2") (pintype "passive"))
      (node (ref "D6") (pin "3") (pinfunction "C_3") (pintype "passive"))
    )
    (net (code "30") (name "Net-(D6-K)") (class "Default")
      (node (ref "C1") (pin "2") (pinfunction "2_2") (pintype "passive"))
      (node (ref "C10") (pin "1") (pinfunction "1_1") (pintype "passive"))
      (node (ref "D6") (pin "2") (pinfunction "K_2") (pintype "passive"))
      (node (ref "D8") (pin "1") (pinfunction "A_1") (pintype "passive"))
    )
    (net (code "31") (name "Net-(D7-C)") (class "Default")
      (node (ref "Cs7") (pin "2") (pinfunction "2_2") (pintype "passive"))
      (node (ref "D7") (pin "3") (pinfunction "C_3") (pintype "passive"))
    )
    (net (code "32") (name "Net-(D7-K)") (class "Default")
      (node (ref "C2") (pin "2") (pinfunction "2_2") (pintype "passive"))
      (node (ref "C6") (pin "1") (pinfunction "1_1") (pintype "passive"))
      (node (ref "D7") (pin "2") (pinfunction "K_2") (pintype "passive"))
      (node (ref "R1") (pin "2") (pinfunction "2_2") (pintype "passive"))
    )
    (net (code "33") (name "Net-(D8-C)") (class "Default")
      (node (ref "Cs8") (pin "2") (pinfunction "2_2") (pintype "passive"))
      (node (ref "D8") (pin "3") (pinfunction "C_3") (pintype "passive"))
    )
    (net (code "34") (name "Net-(Q2-D)") (class "Default")
      (node (ref "Lt_1") (pin "2") (pinfunction "2_2") (pintype "passive"))
      (node (ref "Q2") (pin "2") (pinfunction "D_2") (pintype "passive"))
      (node (ref "uP1") (pin "3") (pinfunction "Pos_3") (pintype "passive"))
    )
    (net (code "35") (name "Net-(SW1-RF1)") (class "Default")
      (node (ref "Ct_2") (pin "1") (pinfunction "1_1") (pintype "passive"))
      (node (ref "Lt_2") (pin "1") (pinfunction "1_1") (pintype "passive"))
      (node (ref "SW1") (pin "8") (pinfunction "RF1_8") (pintype "output"))
    )
    (net (code "36") (name "Net-(SW1-RF2)") (class "Default")
      (node (ref "Ct_1") (pin "2") (pinfunction "2_2") (pintype "passive"))
      (node (ref "Lt_1") (pin "1") (pinfunction "1_1") (pintype "passive"))
      (node (ref "SW1") (pin "5") (pinfunction "RF2_5") (pintype "power_in"))
    )
    (net (code "37") (name "Net-(U2-LBOOST)") (class "Default")
      (node (ref "L1") (pin "2") (pinfunction "2_2") (pintype "passive"))
      (node (ref "U2") (pin "20") (pinfunction "LBOOST_20") (pintype "input"))
    )
    (net (code "38") (name "Net-(U2-OK_HYST)") (class "Default")
      (node (ref "R17") (pin "1") (pinfunction "1_1") (pintype "passive"))
      (node (ref "R18") (pin "2") (pinfunction "2_2") (pintype "passive"))
      (node (ref "U2") (pin "10") (pinfunction "OK_HYST_10") (pintype "input"))
    )
    (net (code "39") (name "Net-(U2-OK_PROG)") (class "Default")
      (node (ref "R16") (pin "1") (pinfunction "1_1") (pintype "passive"))
      (node (ref "R17") (pin "2") (pinfunction "2_2") (pintype "passive"))
      (node (ref "U2") (pin "11") (pinfunction "OK_PROG_11") (pintype "input"))
    )
    (net (code "40") (name "Net-(U2-VBAT_OV)") (class "Default")
      (node (ref "R19") (pin "1") (pinfunction "1_1") (pintype "passive"))
      (node (ref "R20") (pin "2") (pinfunction "2_2") (pintype "passive"))
      (node (ref "U2") (pin "7") (pinfunction "VBAT_OV_7") (pintype "input"))
    )
    (net (code "41") (name "Net-(U2-VOC_SAMP)") (class "Default")
      (node (ref "R21") (pin "1") (pinfunction "1_1") (pintype "passive"))
      (node (ref "R22") (pin "2") (pinfunction "2_2") (pintype "passive"))
      (node (ref "U2") (pin "3") (pinfunction "VOC_SAMP_3") (pintype "input"))
    )
    (net (code "42") (name "Net-(U2-VRDIV)") (class "Default")
      (node (ref "R18") (pin "1") (pinfunction "1_1") (pintype "passive"))
      (node (ref "R20") (pin "1") (pinfunction "1_1") (pintype "passive"))
      (node (ref "U2") (pin "8") (pinfunction "VRDIV_8") (pintype "output"))
    )
    (net (code "43") (name "Vreg") (class "Default")
      (node (ref "C8") (pin "2") (pinfunction "2_2") (pintype "passive"))
      (node (ref "T3") (pin "1") (pintype "passive"))
      (node (ref "U3") (pin "5") (pinfunction "OUT_5") (pintype "power_in"))
    )
    (net (code "44") (name "Vstore") (class "Default")
      (node (ref "C21") (pin "2") (pinfunction "2_2") (pintype "passive"))
      (node (ref "C22") (pin "2") (pinfunction "2_2") (pintype "passive"))
      (node (ref "C27") (pin "2") (pinfunction "2_2") (pintype "passive"))
      (node (ref "R21") (pin "2") (pinfunction "2_2") (pintype "passive"))
      (node (ref "R24") (pin "2") (pinfunction "2_2") (pintype "passive"))
      (node (ref "SW2") (pin "6") (pinfunction "VDD_6") (pintype "passive"))
      (node (ref "T4") (pin "1") (pintype "passive"))
      (node (ref "U2") (pin "19") (pinfunction "VSTOR_19") (pintype "passive"))
      (node (ref "U3") (pin "1") (pinfunction "IN_1") (pintype "power_in"))
      (node (ref "U3") (pin "4") (pinfunction "FB_4") (pintype "input"))
    )
    (net (code "45") (name "unconnected-(SPK1-Sleeve-Pad1)") (class "Default")
      (node (ref "SPK1") (pin "1") (pinfunction "Sleeve_1") (pintype "passive"))
    )
    (net (code "46") (name "unconnected-(SPK1-Tip_Switch-Pad4)") (class "Default")
      (node (ref "SPK1") (pin "4") (pinfunction "Tip_Switch_4") (pintype "passive"))
    )
    (net (code "47") (name "unconnected-(TF1-Pin2-Pad2)") (class "Default")
      (node (ref "TF1") (pin "2") (pinfunction "Pin2_2") (pintype "passive"))
    )
    (net (code "48") (name "unconnected-(TF1-Pin5-Pad5)") (class "Default")
      (node (ref "TF1") (pin "5") (pinfunction "Pin5_5") (pintype "passive"))
    )
    (net (code "49") (name "unconnected-(U2-LBUCK-Pad16)") (class "Default")
      (node (ref "U2") (pin "16") (pinfunction "LBUCK_16") (pintype "passive"))
    )
    (net (code "50") (name "unconnected-(U2-VOUT-Pad14)") (class "Default")
      (node (ref "U2") (pin "14") (pinfunction "VOUT_14") (pintype "passive"))
    )
    (net (code "51") (name "unconnected-(U2-VOUT_SET-Pad12)") (class "Default")
      (node (ref "U2") (pin "12") (pinfunction "VOUT_SET_12") (pintype "input+no_connect"))
    )
  )
)
